# 05_-_AUDIO.net
KiCad netlist of a schematic drawn in Altium Designer
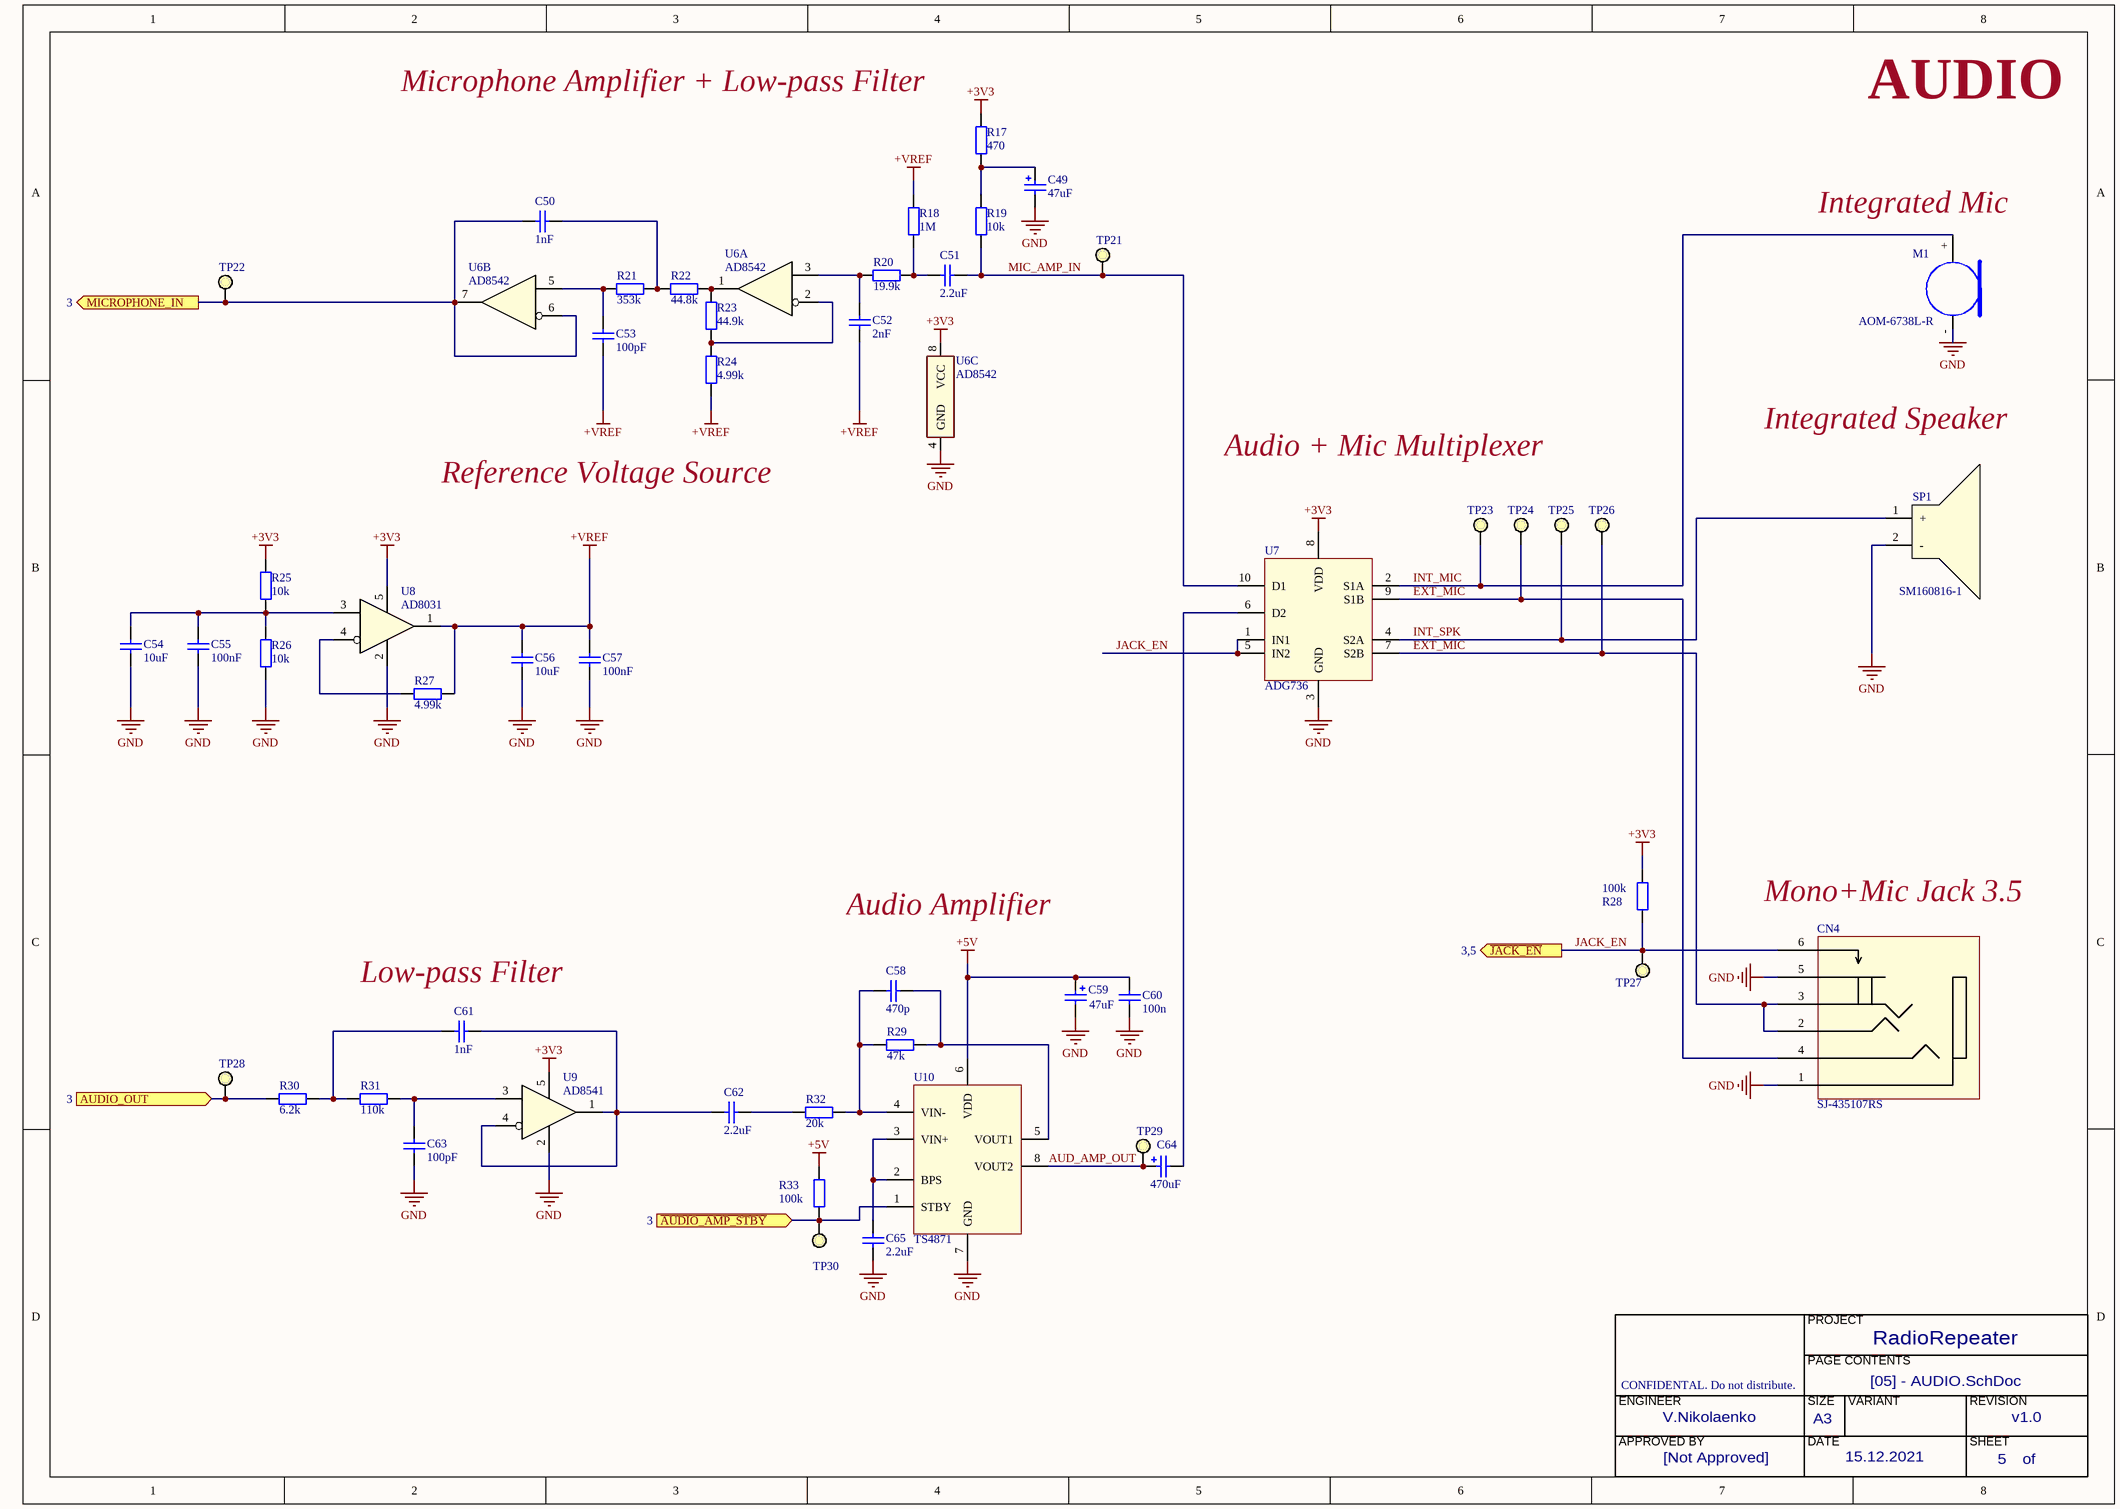
[diagram p0: [05] - AUDIO.SchDoc]

(export (version "E")
  (design (tool "Eeschema 10.0.6"))
  (components
    (comp (ref "C49")
      (value "47uF")
      (footprint "CAPPR2-4x6.8")
      (description "Polarized Capacitor")
      (libsource (lib "PASSIVE&DISCRETE") (part "Cap Pol"))
    )
    (comp (ref "C50")
      (value "1nF")
      (footprint "CAP0402")
      (description "Capacitor")
      (libsource (lib "PASSIVE&DISCRETE") (part "Cap"))
    )
    (comp (ref "C51")
      (value "2.2uF")
      (footprint "CAP0402")
      (description "Capacitor")
      (libsource (lib "PASSIVE&DISCRETE") (part "Cap"))
    )
    (comp (ref "C52")
      (value "2nF")
      (footprint "CAP0402")
      (description "Capacitor")
      (libsource (lib "PASSIVE&DISCRETE") (part "Cap"))
    )
    (comp (ref "C53")
      (value "100pF")
      (footprint "CAP0402")
      (description "Capacitor")
      (libsource (lib "PASSIVE&DISCRETE") (part "Cap"))
    )
    (comp (ref "C54")
      (value "10uF")
      (footprint "CAP0402")
      (description "Capacitor")
      (libsource (lib "PASSIVE&DISCRETE") (part "Cap"))
    )
    (comp (ref "C55")
      (value "100nF")
      (footprint "CAP0402")
      (description "Capacitor")
      (libsource (lib "PASSIVE&DISCRETE") (part "Cap"))
    )
    (comp (ref "C56")
      (value "10uF")
      (footprint "CAP0402")
      (description "Capacitor")
      (libsource (lib "PASSIVE&DISCRETE") (part "Cap"))
    )
    (comp (ref "C57")
      (value "100nF")
      (footprint "CAP0402")
      (description "Capacitor")
      (libsource (lib "PASSIVE&DISCRETE") (part "Cap"))
    )
    (comp (ref "C58")
      (value "470p")
      (footprint "CAP0402")
      (description "Capacitor")
      (libsource (lib "PASSIVE&DISCRETE") (part "Cap"))
    )
    (comp (ref "C59")
      (value "47uF")
      (footprint "CAPPR2-4x6.8")
      (description "Polarized Capacitor")
      (libsource (lib "PASSIVE&DISCRETE") (part "Cap Pol"))
    )
    (comp (ref "C60")
      (value "100n")
      (footprint "CAP0402")
      (description "Capacitor")
      (libsource (lib "PASSIVE&DISCRETE") (part "Cap"))
    )
    (comp (ref "C61")
      (value "1nF")
      (footprint "CAP0402")
      (description "Capacitor")
      (libsource (lib "PASSIVE&DISCRETE") (part "Cap"))
    )
    (comp (ref "C62")
      (value "2.2uF")
      (footprint "CAP0402")
      (description "Capacitor")
      (libsource (lib "PASSIVE&DISCRETE") (part "Cap"))
    )
    (comp (ref "C63")
      (value "100pF")
      (footprint "CAP0402")
      (description "Capacitor")
      (libsource (lib "PASSIVE&DISCRETE") (part "Cap"))
    )
    (comp (ref "C64")
      (value "470uF")
      (footprint "CAPPR2-4x6.8")
      (description "Polarized Capacitor")
      (libsource (lib "PASSIVE&DISCRETE") (part "Cap Pol"))
    )
    (comp (ref "C65")
      (value "2.2uF")
      (footprint "CAP0402")
      (description "Capacitor")
      (libsource (lib "PASSIVE&DISCRETE") (part "Cap"))
    )
    (comp (ref "CN4") (value "SJ-435107RS") (libsource (lib "RadioRepeater") (part "SJ-435107RS")))
    (comp (ref "M1") (value "AOM-6738L-R") (libsource (lib "RadioRepeater") (part "Microphone")))
    (comp (ref "R17")
      (value "470")
      (footprint "RES0402")
      (description "Resistor")
      (libsource (lib "") (part "Res_1"))
    )
    (comp (ref "R18")
      (value "1M")
      (footprint "RES0402")
      (description "Resistor")
      (libsource (lib "") (part "Res_1"))
    )
    (comp (ref "R19")
      (value "10k")
      (footprint "RES0402")
      (description "Resistor")
      (libsource (lib "") (part "Res_1"))
    )
    (comp (ref "R20")
      (value "19.9k")
      (footprint "RES0402")
      (description "Resistor")
      (libsource (lib "") (part "Res_3"))
    )
    (comp (ref "R21")
      (value "353k")
      (footprint "RES0402")
      (description "Resistor")
      (libsource (lib "") (part "Res_3"))
    )
    (comp (ref "R22")
      (value "44.8k")
      (footprint "RES0402")
      (description "Resistor")
      (libsource (lib "") (part "Res_3"))
    )
    (comp (ref "R23")
      (value "44.9k")
      (footprint "RES0402")
      (description "Resistor")
      (libsource (lib "") (part "Res_1"))
    )
    (comp (ref "R24")
      (value "4.99k")
      (footprint "RES0402")
      (description "Resistor")
      (libsource (lib "") (part "Res_1"))
    )
    (comp (ref "R25")
      (value "10k")
      (footprint "RES0402")
      (description "Resistor")
      (libsource (lib "") (part "Res_3"))
    )
    (comp (ref "R26")
      (value "10k")
      (footprint "RES0402")
      (description "Resistor")
      (libsource (lib "") (part "Res_3"))
    )
    (comp (ref "R27")
      (value "4.99k")
      (footprint "RES0402")
      (description "Resistor")
      (libsource (lib "") (part "Res_2"))
    )
    (comp (ref "R28")
      (value "100k")
      (footprint "RES0402")
      (description "Resistor")
      (libsource (lib "PASSIVE&DISCRETE") (part "Res"))
    )
    (comp (ref "R29")
      (value "47k")
      (footprint "RES0402")
      (description "Resistor")
      (libsource (lib "") (part "Res_2"))
    )
    (comp (ref "R30")
      (value "6.2k")
      (footprint "RES0402")
      (description "Resistor")
      (libsource (lib "") (part "Res_1"))
    )
    (comp (ref "R31")
      (value "110k")
      (footprint "RES0402")
      (description "Resistor")
      (libsource (lib "") (part "Res_1"))
    )
    (comp (ref "R32")
      (value "20k")
      (footprint "RES0402")
      (description "Resistor")
      (libsource (lib "") (part "Res_2"))
    )
    (comp (ref "R33")
      (value "100k")
      (footprint "RES0402")
      (description "Resistor")
      (libsource (lib "PASSIVE&DISCRETE") (part "Res"))
    )
    (comp (ref "SP1") (value "SM160816-1") (libsource (lib "ELECTROMECHANICAL") (part "Speaker")))
    (comp (ref "TP21")
      (value "TestPoint")
      (footprint "TestPoint")
      (libsource (lib "CONNECTORS") (part "TestPoint"))
    )
    (comp (ref "TP22")
      (value "TestPoint")
      (footprint "TestPoint")
      (libsource (lib "CONNECTORS") (part "TestPoint"))
    )
    (comp (ref "TP23")
      (value "TestPoint")
      (footprint "TestPoint")
      (libsource (lib "CONNECTORS") (part "TestPoint"))
    )
    (comp (ref "TP24")
      (value "TestPoint")
      (footprint "TestPoint")
      (libsource (lib "CONNECTORS") (part "TestPoint"))
    )
    (comp (ref "TP25")
      (value "TestPoint")
      (footprint "TestPoint")
      (libsource (lib "CONNECTORS") (part "TestPoint"))
    )
    (comp (ref "TP26")
      (value "TestPoint")
      (footprint "TestPoint")
      (libsource (lib "CONNECTORS") (part "TestPoint"))
    )
    (comp (ref "TP27")
      (value "TestPoint")
      (footprint "TestPoint")
      (libsource (lib "CONNECTORS") (part "TestPoint"))
    )
    (comp (ref "TP28")
      (value "TestPoint")
      (footprint "TestPoint")
      (libsource (lib "CONNECTORS") (part "TestPoint"))
    )
    (comp (ref "TP29")
      (value "TestPoint")
      (footprint "TestPoint")
      (libsource (lib "CONNECTORS") (part "TestPoint"))
    )
    (comp (ref "TP30")
      (value "TestPoint")
      (footprint "TestPoint")
      (libsource (lib "CONNECTORS") (part "TestPoint"))
    )
    (comp (ref "U6") (value "AD8542") (footprint "SOIC8") (libsource (lib "MISCELLANEOUS") (part "OPAMP x2")))
    (comp (ref "U7") (value "ADG736") (libsource (lib "RadioRepeater") (part "ADG736")))
    (comp (ref "U8")
      (value "AD8031")
      (footprint "SOT23-5_PITCH0.95")
      (libsource (lib "MISCELLANEOUS") (part "OPAMP x1"))
    )
    (comp (ref "U9")
      (value "AD8541")
      (footprint "SOT23-5_PITCH0.95")
      (libsource (lib "MISCELLANEOUS") (part "OPAMP x1"))
    )
    (comp (ref "U10") (value "TS4871") (libsource (lib "RadioRepeater") (part "TS4871")))
  )
  (nets
    (net (code "1") (name "+3V3") (class "Default")
      (node (ref "R17") (pin "2") (pinfunction "2_2") (pintype "passive"))
      (node (ref "R25") (pin "2") (pinfunction "2_2") (pintype "passive"))
      (node (ref "R28") (pin "1") (pinfunction "1_1") (pintype "passive"))
      (node (ref "U6") (pin "8") (pinfunction "VCC_8") (pintype "power_in"))
      (node (ref "U7") (pin "8") (pinfunction "VDD_8") (pintype "passive"))
      (node (ref "U8") (pin "5") (pinfunction "VCC+_5") (pintype "passive"))
      (node (ref "U9") (pin "5") (pinfunction "VCC+_5") (pintype "passive"))
    )
    (net (code "2") (name "+5V") (class "Default")
      (node (ref "C59") (pin "1") (pinfunction "1_1") (pintype "passive"))
      (node (ref "C60") (pin "2") (pinfunction "2_2") (pintype "passive"))
      (node (ref "R33") (pin "1") (pinfunction "1_1") (pintype "passive"))
      (node (ref "U10") (pin "6") (pinfunction "VDD_6") (pintype "passive"))
    )
    (net (code "3") (name "+VREF") (class "Default")
      (node (ref "C52") (pin "1") (pinfunction "1_1") (pintype "passive"))
      (node (ref "C53") (pin "1") (pinfunction "1_1") (pintype "passive"))
      (node (ref "C56") (pin "2") (pinfunction "2_2") (pintype "passive"))
      (node (ref "C57") (pin "2") (pinfunction "2_2") (pintype "passive"))
      (node (ref "R18") (pin "2") (pinfunction "2_2") (pintype "passive"))
      (node (ref "R24") (pin "1") (pinfunction "1_1") (pintype "passive"))
      (node (ref "R27") (pin "1") (pinfunction "1_1") (pintype "passive"))
      (node (ref "U8") (pin "1") (pinfunction "OUT_1") (pintype "passive"))
    )
    (net (code "4") (name "/AUDIO_OUT") (class "Default")
      (node (ref "R30") (pin "1") (pinfunction "1_1") (pintype "passive"))
      (node (ref "TP28") (pin "1") (pinfunction "1_1") (pintype "passive"))
    )
    (net (code "5") (name "/AUD_AMP_OUT") (class "Default")
      (node (ref "C64") (pin "1") (pinfunction "1_1") (pintype "passive"))
      (node (ref "TP29") (pin "1") (pinfunction "1_1") (pintype "passive"))
      (node (ref "U10") (pin "8") (pinfunction "VOUT2_8") (pintype "passive"))
    )
    (net (code "6") (name "/EXT_MIC") (class "Default")
      (node (ref "CN4") (pin "2") (pinfunction "2_2") (pintype "passive"))
      (node (ref "CN4") (pin "3") (pinfunction "3_3") (pintype "passive"))
      (node (ref "CN4") (pin "4") (pinfunction "4_4") (pintype "passive"))
      (node (ref "TP24") (pin "1") (pinfunction "1_1") (pintype "passive"))
      (node (ref "TP26") (pin "1") (pinfunction "1_1") (pintype "passive"))
      (node (ref "U7") (pin "7") (pinfunction "S2B_7") (pintype "passive"))
      (node (ref "U7") (pin "9") (pinfunction "S1B_9") (pintype "passive"))
    )
    (net (code "7") (name "/INT_MIC") (class "Default")
      (node (ref "M1") (pin "+") (pinfunction "0_+") (pintype "passive"))
      (node (ref "TP23") (pin "1") (pinfunction "1_1") (pintype "passive"))
      (node (ref "U7") (pin "2") (pinfunction "S1A_2") (pintype "passive"))
    )
    (net (code "8") (name "/INT_SPK") (class "Default")
      (node (ref "SP1") (pin "1") (pinfunction "+_1") (pintype "passive"))
      (node (ref "TP25") (pin "1") (pinfunction "1_1") (pintype "passive"))
      (node (ref "U7") (pin "4") (pinfunction "S2A_4") (pintype "passive"))
    )
    (net (code "9") (name "/JACK_EN") (class "Default")
      (node (ref "CN4") (pin "6") (pinfunction "6_6") (pintype "passive"))
      (node (ref "R28") (pin "2") (pinfunction "2_2") (pintype "passive"))
      (node (ref "TP27") (pin "1") (pinfunction "1_1") (pintype "passive"))
      (node (ref "U7") (pin "1") (pinfunction "IN1_1") (pintype "passive"))
      (node (ref "U7") (pin "5") (pinfunction "IN2_5") (pintype "passive"))
    )
    (net (code "10") (name "/MICROPHONE_IN") (class "Default")
      (node (ref "C50") (pin "2") (pinfunction "2_2") (pintype "passive"))
      (node (ref "TP22") (pin "1") (pinfunction "1_1") (pintype "passive"))
      (node (ref "U6") (pin "6") (pinfunction "IN-_6") (pintype "passive"))
      (node (ref "U6") (pin "7") (pinfunction "OUT_7") (pintype "passive"))
    )
    (net (code "11") (name "/MIC_AMP_IN") (class "Default")
      (node (ref "C51") (pin "1") (pinfunction "1_1") (pintype "passive"))
      (node (ref "R19") (pin "1") (pinfunction "1_1") (pintype "passive"))
      (node (ref "TP21") (pin "1") (pinfunction "1_1") (pintype "passive"))
      (node (ref "U7") (pin "10") (pinfunction "D1_10") (pintype "passive"))
    )
    (net (code "12") (name "/~{AUDIO_AMP_STBY}") (class "Default")
      (node (ref "R33") (pin "2") (pinfunction "2_2") (pintype "passive"))
      (node (ref "TP30") (pin "1") (pinfunction "1_1") (pintype "passive"))
      (node (ref "U10") (pin "1") (pinfunction "STBY_1") (pintype "passive"))
    )
    (net (code "13") (name "GND") (class "Default")
      (node (ref "C49") (pin "2") (pinfunction "2_2") (pintype "passive"))
      (node (ref "C54") (pin "1") (pinfunction "1_1") (pintype "passive"))
      (node (ref "C55") (pin "1") (pinfunction "1_1") (pintype "passive"))
      (node (ref "C56") (pin "1") (pinfunction "1_1") (pintype "passive"))
      (node (ref "C57") (pin "1") (pinfunction "1_1") (pintype "passive"))
      (node (ref "C59") (pin "2") (pinfunction "2_2") (pintype "passive"))
      (node (ref "C60") (pin "1") (pinfunction "1_1") (pintype "passive"))
      (node (ref "C63") (pin "1") (pinfunction "1_1") (pintype "passive"))
      (node (ref "C65") (pin "1") (pinfunction "1_1") (pintype "passive"))
      (node (ref "CN4") (pin "1") (pinfunction "1_1") (pintype "passive"))
      (node (ref "CN4") (pin "5") (pinfunction "5_5") (pintype "passive"))
      (node (ref "M1") (pin "-") (pinfunction "1_-") (pintype "passive"))
      (node (ref "R26") (pin "1") (pinfunction "1_1") (pintype "passive"))
      (node (ref "SP1") (pin "2") (pinfunction "-_2") (pintype "passive"))
      (node (ref "U10") (pin "7") (pinfunction "GND_7") (pintype "passive"))
      (node (ref "U6") (pin "4") (pinfunction "GND_4") (pintype "power_in"))
      (node (ref "U7") (pin "3") (pinfunction "GND_3") (pintype "passive"))
      (node (ref "U8") (pin "2") (pinfunction "VCC-_2") (pintype "passive"))
      (node (ref "U9") (pin "2") (pinfunction "VCC-_2") (pintype "passive"))
    )
    (net (code "14") (name "Net-(C49-Pad1)") (class "Default")
      (node (ref "C49") (pin "1") (pinfunction "1_1") (pintype "passive"))
      (node (ref "R17") (pin "1") (pinfunction "1_1") (pintype "passive"))
      (node (ref "R19") (pin "2") (pinfunction "2_2") (pintype "passive"))
    )
    (net (code "15") (name "Net-(C50-Pad1)") (class "Default")
      (node (ref "C50") (pin "1") (pinfunction "1_1") (pintype "passive"))
      (node (ref "R21") (pin "2") (pinfunction "2_2") (pintype "passive"))
      (node (ref "R22") (pin "1") (pinfunction "1_1") (pintype "passive"))
    )
    (net (code "16") (name "Net-(C51-Pad2)") (class "Default")
      (node (ref "C51") (pin "2") (pinfunction "2_2") (pintype "passive"))
      (node (ref "R18") (pin "1") (pinfunction "1_1") (pintype "passive"))
      (node (ref "R20") (pin "2") (pinfunction "2_2") (pintype "passive"))
    )
    (net (code "17") (name "Net-(C61-Pad1)") (class "Default")
      (node (ref "C61") (pin "1") (pinfunction "1_1") (pintype "passive"))
      (node (ref "R30") (pin "2") (pinfunction "2_2") (pintype "passive"))
      (node (ref "R31") (pin "1") (pinfunction "1_1") (pintype "passive"))
    )
    (net (code "18") (name "Net-(C62-Pad2)") (class "Default")
      (node (ref "C62") (pin "2") (pinfunction "2_2") (pintype "passive"))
      (node (ref "R32") (pin "2") (pinfunction "2_2") (pintype "passive"))
    )
    (net (code "19") (name "Net-(U6A-IN+)") (class "Default")
      (node (ref "C52") (pin "2") (pinfunction "2_2") (pintype "passive"))
      (node (ref "R20") (pin "1") (pinfunction "1_1") (pintype "passive"))
      (node (ref "U6") (pin "3") (pinfunction "IN+_3") (pintype "passive"))
    )
    (net (code "20") (name "Net-(U6A-IN-)") (class "Default")
      (node (ref "R23") (pin "1") (pinfunction "1_1") (pintype "passive"))
      (node (ref "R24") (pin "2") (pinfunction "2_2") (pintype "passive"))
      (node (ref "U6") (pin "2") (pinfunction "IN-_2") (pintype "passive"))
    )
    (net (code "21") (name "Net-(U6A-OUT)") (class "Default")
      (node (ref "R22") (pin "2") (pinfunction "2_2") (pintype "passive"))
      (node (ref "R23") (pin "2") (pinfunction "2_2") (pintype "passive"))
      (node (ref "U6") (pin "1") (pinfunction "OUT_1") (pintype "passive"))
    )
    (net (code "22") (name "Net-(U6B-IN+)") (class "Default")
      (node (ref "C53") (pin "2") (pinfunction "2_2") (pintype "passive"))
      (node (ref "R21") (pin "1") (pinfunction "1_1") (pintype "passive"))
      (node (ref "U6") (pin "5") (pinfunction "IN+_5") (pintype "passive"))
    )
    (net (code "23") (name "Net-(U7-D2)") (class "Default")
      (node (ref "C64") (pin "2") (pinfunction "2_2") (pintype "passive"))
      (node (ref "U7") (pin "6") (pinfunction "D2_6") (pintype "passive"))
    )
    (net (code "24") (name "Net-(U8-IN+)") (class "Default")
      (node (ref "C54") (pin "2") (pinfunction "2_2") (pintype "passive"))
      (node (ref "C55") (pin "2") (pinfunction "2_2") (pintype "passive"))
      (node (ref "R25") (pin "1") (pinfunction "1_1") (pintype "passive"))
      (node (ref "R26") (pin "2") (pinfunction "2_2") (pintype "passive"))
      (node (ref "U8") (pin "3") (pinfunction "IN+_3") (pintype "passive"))
    )
    (net (code "25") (name "Net-(U8-IN-)") (class "Default")
      (node (ref "R27") (pin "2") (pinfunction "2_2") (pintype "passive"))
      (node (ref "U8") (pin "4") (pinfunction "IN-_4") (pintype "passive"))
    )
    (net (code "26") (name "Net-(U9-IN+)") (class "Default")
      (node (ref "C63") (pin "2") (pinfunction "2_2") (pintype "passive"))
      (node (ref "R31") (pin "2") (pinfunction "2_2") (pintype "passive"))
      (node (ref "U9") (pin "3") (pinfunction "IN+_3") (pintype "passive"))
    )
    (net (code "27") (name "Net-(U9-IN-)") (class "Default")
      (node (ref "C61") (pin "2") (pinfunction "2_2") (pintype "passive"))
      (node (ref "C62") (pin "1") (pinfunction "1_1") (pintype "passive"))
      (node (ref "U9") (pin "1") (pinfunction "OUT_1") (pintype "passive"))
      (node (ref "U9") (pin "4") (pinfunction "IN-_4") (pintype "passive"))
    )
    (net (code "28") (name "Net-(U10-BPS)") (class "Default")
      (node (ref "C65") (pin "2") (pinfunction "2_2") (pintype "passive"))
      (node (ref "U10") (pin "2") (pinfunction "BPS_2") (pintype "passive"))
      (node (ref "U10") (pin "3") (pinfunction "VIN+_3") (pintype "passive"))
    )
    (net (code "29") (name "Net-(U10-VIN-)") (class "Default")
      (node (ref "C58") (pin "1") (pinfunction "1_1") (pintype "passive"))
      (node (ref "R29") (pin "2") (pinfunction "2_2") (pintype "passive"))
      (node (ref "R32") (pin "1") (pinfunction "1_1") (pintype "passive"))
      (node (ref "U10") (pin "4") (pinfunction "VIN-_4") (pintype "passive"))
    )
    (net (code "30") (name "Net-(U10-VOUT1)") (class "Default")
      (node (ref "C58") (pin "2") (pinfunction "2_2") (pintype "passive"))
      (node (ref "R29") (pin "1") (pinfunction "1_1") (pintype "passive"))
      (node (ref "U10") (pin "5") (pinfunction "VOUT1_5") (pintype "passive"))
    )
  )
)
